# IOMOD-SW8B-v1_0.net
KiCad netlist of a schematic drawn in EAGLE
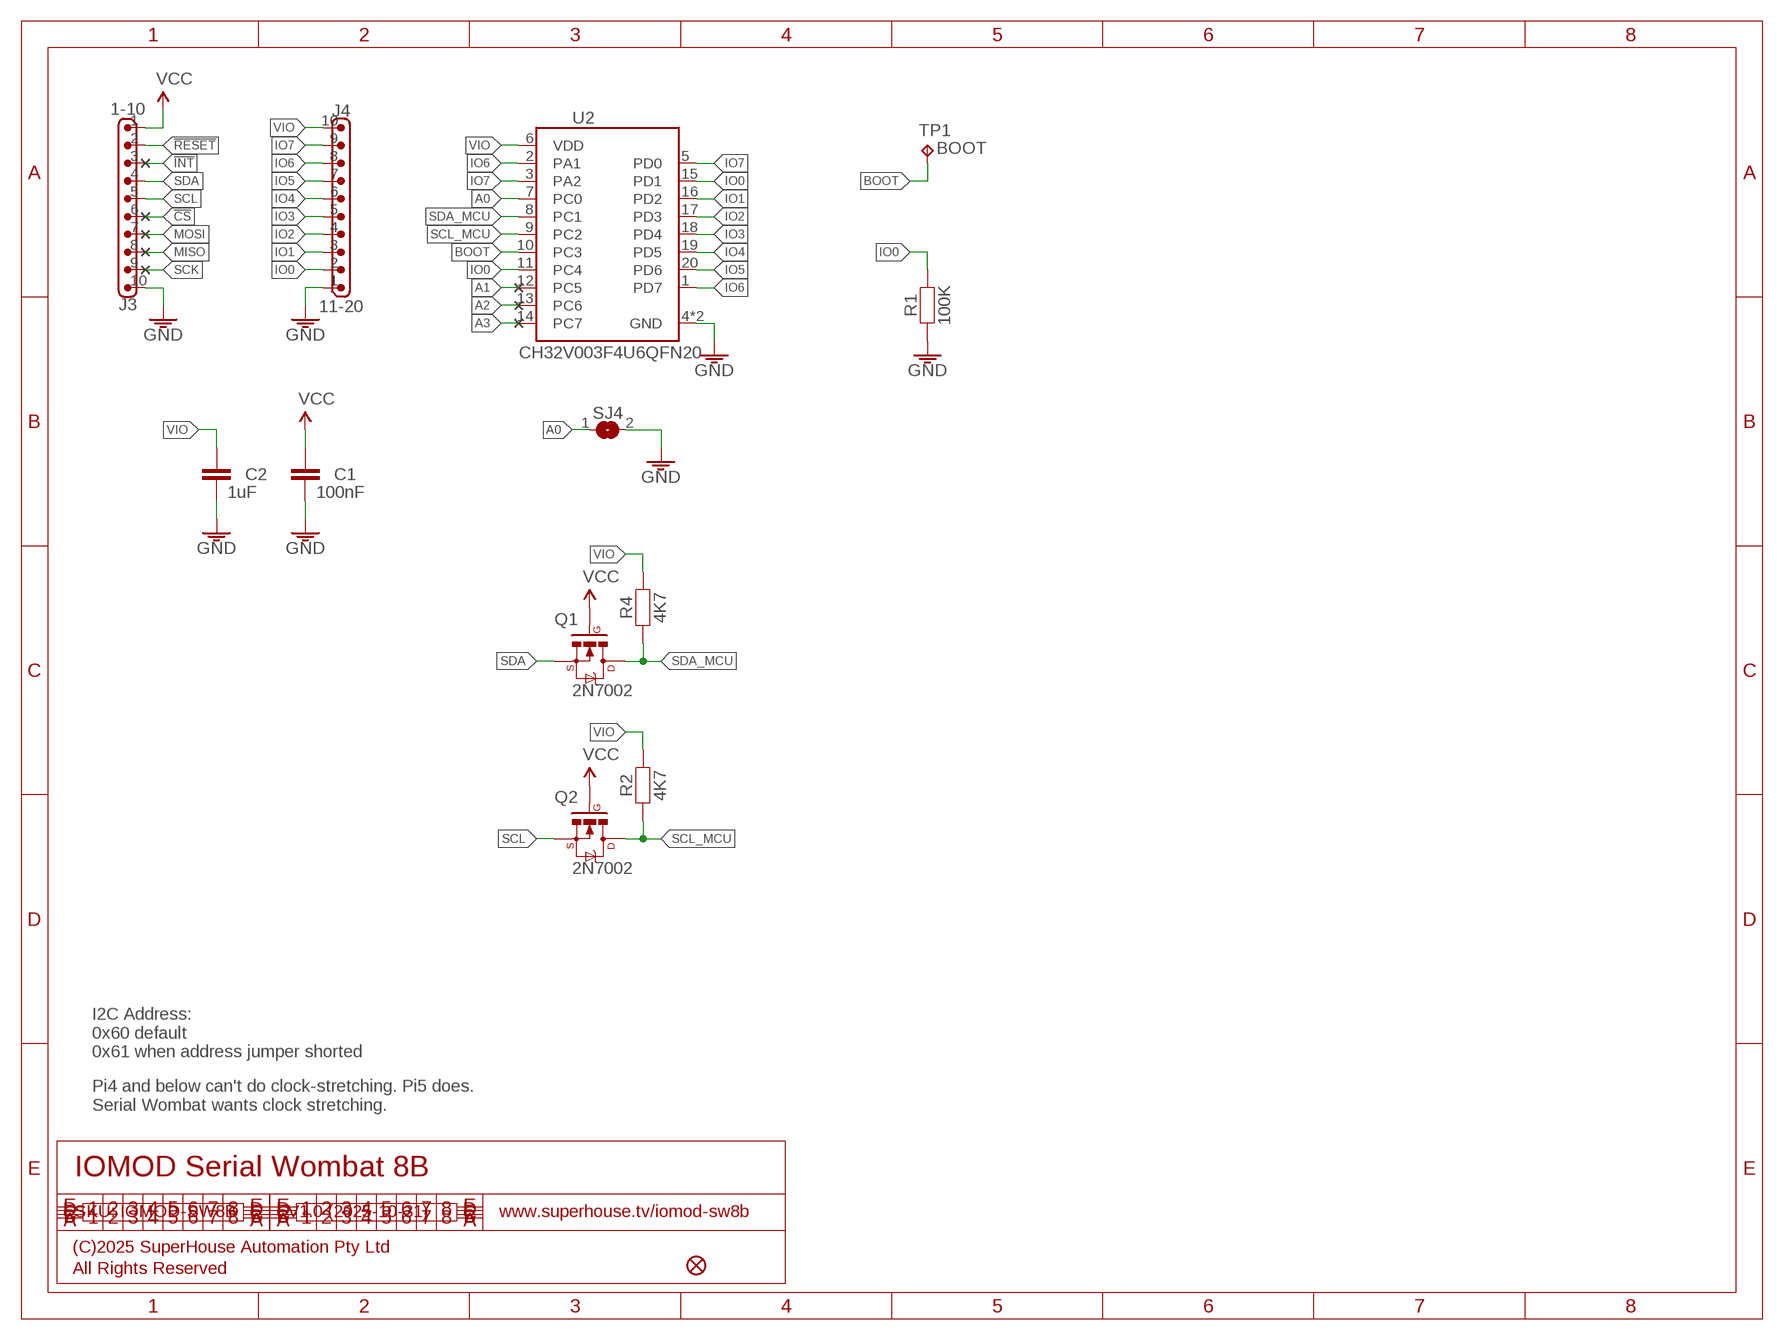
[diagram p0: schematic, sheet 1]

(export (version "E")
  (design (tool "Eeschema 10.0.6"))
  (components
    (comp (ref "C1")
      (value "100nF")
      (footprint "eagle-import:C0603")
      (libsource (lib "eagle-import") (part "CAP0603"))
    )
    (comp (ref "C2")
      (value "1uF")
      (footprint "eagle-import:C0603")
      (libsource (lib "eagle-import") (part "CAP0603"))
    )
    (comp (ref "FID1")
      (value "FIDUCIAL1X2.5")
      (footprint "eagle-import:FIDUCIAL-1X2.5")
      (libsource (lib "eagle-import") (part "FIDUCIAL1X2.5"))
    )
    (comp (ref "J3")
      (value "1-10")
      (footprint "eagle-import:1X10-2.00-P-ABOVE")
      (libsource (lib "eagle-import") (part "M10-2.00-P-ABOVE"))
    )
    (comp (ref "J4")
      (value "11-20")
      (footprint "eagle-import:1X10-2.00-P-ABOVE")
      (libsource (lib "eagle-import") (part "M10-2.00-P-ABOVE"))
    )
    (comp (ref "Q1")
      (value "2N7002")
      (footprint "eagle-import:SOT23-3")
      (libsource (lib "eagle-import") (part "MOSFET-NCHANNEL-233"))
    )
    (comp (ref "Q2")
      (value "2N7002")
      (footprint "eagle-import:SOT23-3")
      (libsource (lib "eagle-import") (part "MOSFET-NCHANNEL-233"))
    )
    (comp (ref "R1")
      (value "100K")
      (footprint "eagle-import:R0603")
      (libsource (lib "eagle-import") (part "RESISTOR0603"))
    )
    (comp (ref "R2")
      (value "4K7")
      (footprint "eagle-import:R0603")
      (libsource (lib "eagle-import") (part "RESISTOR0603"))
    )
    (comp (ref "R4")
      (value "4K7")
      (footprint "eagle-import:R0603")
      (libsource (lib "eagle-import") (part "RESISTOR0603"))
    )
    (comp (ref "SJ4")
      (value "SJ-NORMAL")
      (footprint "eagle-import:SJ")
      (libsource (lib "eagle-import") (part "SJ-NORMAL"))
    )
    (comp (ref "TP1")
      (value "BOOT")
      (footprint "eagle-import:B1,27")
      (libsource (lib "eagle-import") (part "TPB1,27"))
    )
    (comp (ref "U2")
      (value "CH32V003F4U6QFN20")
      (footprint "eagle-import:QFN-20")
      (libsource (lib "eagle-import") (part "CH32V003F4U6QFN20"))
    )
  )
  (nets
    (net (code "1") (name "/~{CS}") (class "Default")
      (node (ref "J3") (pin "6") (pinfunction "6_6") (pintype "passive"))
    )
    (net (code "2") (name "/~{INT}") (class "Default")
      (node (ref "J3") (pin "3") (pinfunction "3_3") (pintype "passive"))
    )
    (net (code "3") (name "/~{RESET}") (class "Default")
      (node (ref "J3") (pin "2") (pinfunction "2_2") (pintype "passive"))
    )
    (net (code "4") (name "A0") (class "Default")
      (node (ref "SJ4") (pin "1") (pinfunction "1_1") (pintype "passive"))
      (node (ref "U2") (pin "7") (pinfunction "PC0_7") (pintype "bidirectional"))
    )
    (net (code "5") (name "A1") (class "Default")
      (node (ref "U2") (pin "12") (pinfunction "PC5_12") (pintype "bidirectional"))
    )
    (net (code "6") (name "A2") (class "Default")
      (node (ref "U2") (pin "13") (pinfunction "PC6_13") (pintype "bidirectional"))
    )
    (net (code "7") (name "A3") (class "Default")
      (node (ref "U2") (pin "14") (pinfunction "PC7_14") (pintype "bidirectional"))
    )
    (net (code "8") (name "BOOT") (class "Default")
      (node (ref "TP1") (pin "TP") (pinfunction "TP_TP") (pintype "input"))
      (node (ref "U2") (pin "10") (pinfunction "PC3_10") (pintype "bidirectional"))
    )
    (net (code "9") (name "GND") (class "Default")
      (node (ref "C1") (pin "2") (pinfunction "2_2") (pintype "passive"))
      (node (ref "C2") (pin "2") (pinfunction "2_2") (pintype "passive"))
      (node (ref "J3") (pin "10") (pinfunction "10_10") (pintype "passive"))
      (node (ref "J4") (pin "1") (pinfunction "1_1") (pintype "passive"))
      (node (ref "R1") (pin "1") (pinfunction "1_1") (pintype "passive"))
      (node (ref "SJ4") (pin "2") (pinfunction "2_2") (pintype "passive"))
      (node (ref "U2") (pin "21") (pinfunction "GND_21") (pintype "bidirectional"))
      (node (ref "U2") (pin "4") (pinfunction "GND_4") (pintype "bidirectional"))
    )
    (net (code "10") (name "IO0") (class "Default")
      (node (ref "J4") (pin "2") (pinfunction "2_2") (pintype "passive"))
      (node (ref "R1") (pin "2") (pinfunction "2_2") (pintype "passive"))
      (node (ref "U2") (pin "11") (pinfunction "PC4_11") (pintype "bidirectional"))
      (node (ref "U2") (pin "15") (pinfunction "PD1_15") (pintype "bidirectional"))
    )
    (net (code "11") (name "IO1") (class "Default")
      (node (ref "J4") (pin "3") (pinfunction "3_3") (pintype "passive"))
      (node (ref "U2") (pin "16") (pinfunction "PD2_16") (pintype "bidirectional"))
    )
    (net (code "12") (name "IO2") (class "Default")
      (node (ref "J4") (pin "4") (pinfunction "4_4") (pintype "passive"))
      (node (ref "U2") (pin "17") (pinfunction "PD3_17") (pintype "bidirectional"))
    )
    (net (code "13") (name "IO3") (class "Default")
      (node (ref "J4") (pin "5") (pinfunction "5_5") (pintype "passive"))
      (node (ref "U2") (pin "18") (pinfunction "PD4_18") (pintype "bidirectional"))
    )
    (net (code "14") (name "IO4") (class "Default")
      (node (ref "J4") (pin "6") (pinfunction "6_6") (pintype "passive"))
      (node (ref "U2") (pin "19") (pinfunction "PD5_19") (pintype "bidirectional"))
    )
    (net (code "15") (name "IO5") (class "Default")
      (node (ref "J4") (pin "7") (pinfunction "7_7") (pintype "passive"))
      (node (ref "U2") (pin "20") (pinfunction "PD6_20") (pintype "bidirectional"))
    )
    (net (code "16") (name "IO6") (class "Default")
      (node (ref "J4") (pin "8") (pinfunction "8_8") (pintype "passive"))
      (node (ref "U2") (pin "1") (pinfunction "PD7_1") (pintype "bidirectional"))
      (node (ref "U2") (pin "2") (pinfunction "PA1_2") (pintype "bidirectional"))
    )
    (net (code "17") (name "IO7") (class "Default")
      (node (ref "J4") (pin "9") (pinfunction "9_9") (pintype "passive"))
      (node (ref "U2") (pin "3") (pinfunction "PA2_3") (pintype "bidirectional"))
      (node (ref "U2") (pin "5") (pinfunction "PD0_5") (pintype "bidirectional"))
    )
    (net (code "18") (name "MISO") (class "Default")
      (node (ref "J3") (pin "8") (pinfunction "8_8") (pintype "passive"))
    )
    (net (code "19") (name "MOSI") (class "Default")
      (node (ref "J3") (pin "7") (pinfunction "7_7") (pintype "passive"))
    )
    (net (code "20") (name "SCK") (class "Default")
      (node (ref "J3") (pin "9") (pinfunction "9_9") (pintype "passive"))
    )
    (net (code "21") (name "SCL") (class "Default")
      (node (ref "J3") (pin "5") (pinfunction "5_5") (pintype "passive"))
      (node (ref "Q2") (pin "2") (pinfunction "S_2") (pintype "passive"))
    )
    (net (code "22") (name "SCL_MCU") (class "Default")
      (node (ref "Q2") (pin "3") (pinfunction "D_3") (pintype "passive"))
      (node (ref "R2") (pin "1") (pinfunction "1_1") (pintype "passive"))
      (node (ref "U2") (pin "9") (pinfunction "PC2_9") (pintype "bidirectional"))
    )
    (net (code "23") (name "SDA") (class "Default")
      (node (ref "J3") (pin "4") (pinfunction "4_4") (pintype "passive"))
      (node (ref "Q1") (pin "2") (pinfunction "S_2") (pintype "passive"))
    )
    (net (code "24") (name "SDA_MCU") (class "Default")
      (node (ref "Q1") (pin "3") (pinfunction "D_3") (pintype "passive"))
      (node (ref "R4") (pin "1") (pinfunction "1_1") (pintype "passive"))
      (node (ref "U2") (pin "8") (pinfunction "PC1_8") (pintype "bidirectional"))
    )
    (net (code "25") (name "VCC") (class "Default")
      (node (ref "C1") (pin "1") (pinfunction "1_1") (pintype "passive"))
      (node (ref "J3") (pin "1") (pinfunction "1_1") (pintype "passive"))
      (node (ref "Q1") (pin "1") (pinfunction "G_1") (pintype "passive"))
      (node (ref "Q2") (pin "1") (pinfunction "G_1") (pintype "passive"))
    )
    (net (code "26") (name "VIO") (class "Default")
      (node (ref "C2") (pin "1") (pinfunction "1_1") (pintype "passive"))
      (node (ref "J4") (pin "10") (pinfunction "10_10") (pintype "passive"))
      (node (ref "R2") (pin "2") (pinfunction "2_2") (pintype "passive"))
      (node (ref "R4") (pin "2") (pinfunction "2_2") (pintype "passive"))
      (node (ref "U2") (pin "6") (pinfunction "VDD_6") (pintype "bidirectional"))
    )
  )
)
